# universal_DC-DC.net
KiCad netlist of a schematic drawn in Altium Designer
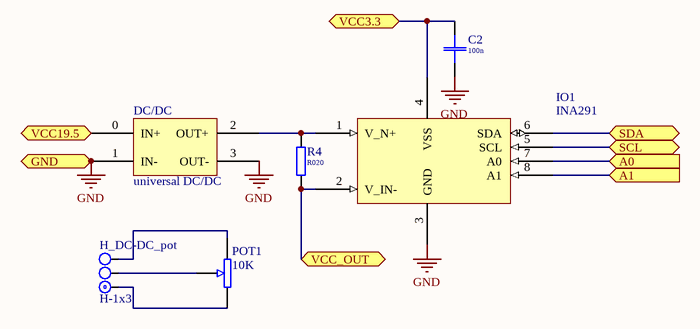
[diagram p0: universal_DC-DC.SchDoc]

(export (version "E")
  (design (tool "Eeschema 10.0.6"))
  (components
    (comp (ref "C2")
      (value "100n")
      (footprint "C0805(2013)")
      (description "SMD-0805 100V X7R 10%")
      (libsource (lib "SMD-RCL") (part "C-0805  100V 10n"))
    )
    (comp (ref "DC/DC")
      (value "universal DC/DC")
      (footprint "MP1584EN dc/dc 3A vertical")
      (libsource (lib "Altium_okruh_miscLib") (part "universal DC/DC"))
    )
    (comp (ref "H_DC-DC_pot") (value "H-1x3") (footprint "J1x3") (libsource (lib "Connektor") (part "H-1x3")))
    (comp (ref "IO1")
      (value "INA291")
      (footprint "SOT23-8L")
      (description "Zerø-Drift, Bi-Directional  CURRENT/POWER MONITOR with I2C™ Interface")
      (libsource (lib "Altium_okruh_miscLib") (part "INA291"))
    )
    (comp (ref "POT1")
      (value "10K")
      (footprint "3590  potenciometer")
      (libsource (lib "Altium_okruh_miscLib") (part "Potenciometer"))
    )
    (comp (ref "R4")
      (value "R020")
      (footprint "R2512")
      (description "SMD 0805 0.1W 5% 150V")
      (libsource (lib "SMD-RCL") (part "R-0805"))
    )
  )
  (nets
    (net (code "1") (name "/A0") (class "Default")
      (node (ref "IO1") (pin "7") (pinfunction "A0_7") (pintype "input"))
    )
    (net (code "2") (name "/A1") (class "Default")
      (node (ref "IO1") (pin "8") (pinfunction "A1_8") (pintype "input"))
    )
    (net (code "3") (name "/SCL") (class "Default")
      (node (ref "IO1") (pin "5") (pinfunction "SCL_5") (pintype "input"))
    )
    (net (code "4") (name "/SDA") (class "Default")
      (node (ref "IO1") (pin "6") (pinfunction "SDA_6") (pintype "bidirectional"))
    )
    (net (code "5") (name "/VCC3.3") (class "Default")
      (node (ref "C2") (pin "1") (pinfunction "1_1") (pintype "passive"))
      (node (ref "IO1") (pin "4") (pinfunction "VSS_4") (pintype "power_in"))
    )
    (net (code "6") (name "/VCC19.5") (class "Default")
      (node (ref "DC/DC") (pin "0") (pinfunction "IN+_0") (pintype "power_in"))
    )
    (net (code "7") (name "/VCC_OUT") (class "Default")
      (node (ref "IO1") (pin "2") (pinfunction "V_IN-_2") (pintype "input"))
      (node (ref "R4") (pin "2") (pinfunction "2_2") (pintype "passive"))
    )
    (net (code "8") (name "GND") (class "Default")
      (node (ref "C2") (pin "2") (pinfunction "2_2") (pintype "passive"))
      (node (ref "DC/DC") (pin "1") (pinfunction "IN-_1") (pintype "power_in"))
      (node (ref "DC/DC") (pin "3") (pinfunction "OUT-_3") (pintype "power_in"))
      (node (ref "IO1") (pin "3") (pinfunction "GND_3") (pintype "power_in"))
    )
    (net (code "9") (name "Net-(DC/DC-OUT+)") (class "Default")
      (node (ref "DC/DC") (pin "2") (pinfunction "OUT+_2") (pintype "power_in"))
      (node (ref "IO1") (pin "1") (pinfunction "V_N+_1") (pintype "input"))
      (node (ref "R4") (pin "1") (pinfunction "1_1") (pintype "passive"))
    )
    (net (code "10") (name "Net-(H_DC-DC_pot-Pad1)") (class "Default")
      (node (ref "H_DC-DC_pot") (pin "1") (pinfunction "1_1") (pintype "passive"))
      (node (ref "POT1") (pin "3") (pinfunction "3_3") (pintype "passive"))
    )
    (net (code "11") (name "Net-(H_DC-DC_pot-Pad2)") (class "Default")
      (node (ref "H_DC-DC_pot") (pin "2") (pinfunction "2_2") (pintype "passive"))
      (node (ref "POT1") (pin "2") (pinfunction "2_2") (pintype "passive"))
    )
    (net (code "12") (name "Net-(H_DC-DC_pot-Pad3)") (class "Default")
      (node (ref "H_DC-DC_pot") (pin "3") (pinfunction "3_3") (pintype "passive"))
      (node (ref "POT1") (pin "1") (pinfunction "1_1") (pintype "passive"))
    )
  )
)
